# DC_Motor_Controller_with_SLAVE_OUT.net
KiCad netlist of a schematic drawn in EAGLE
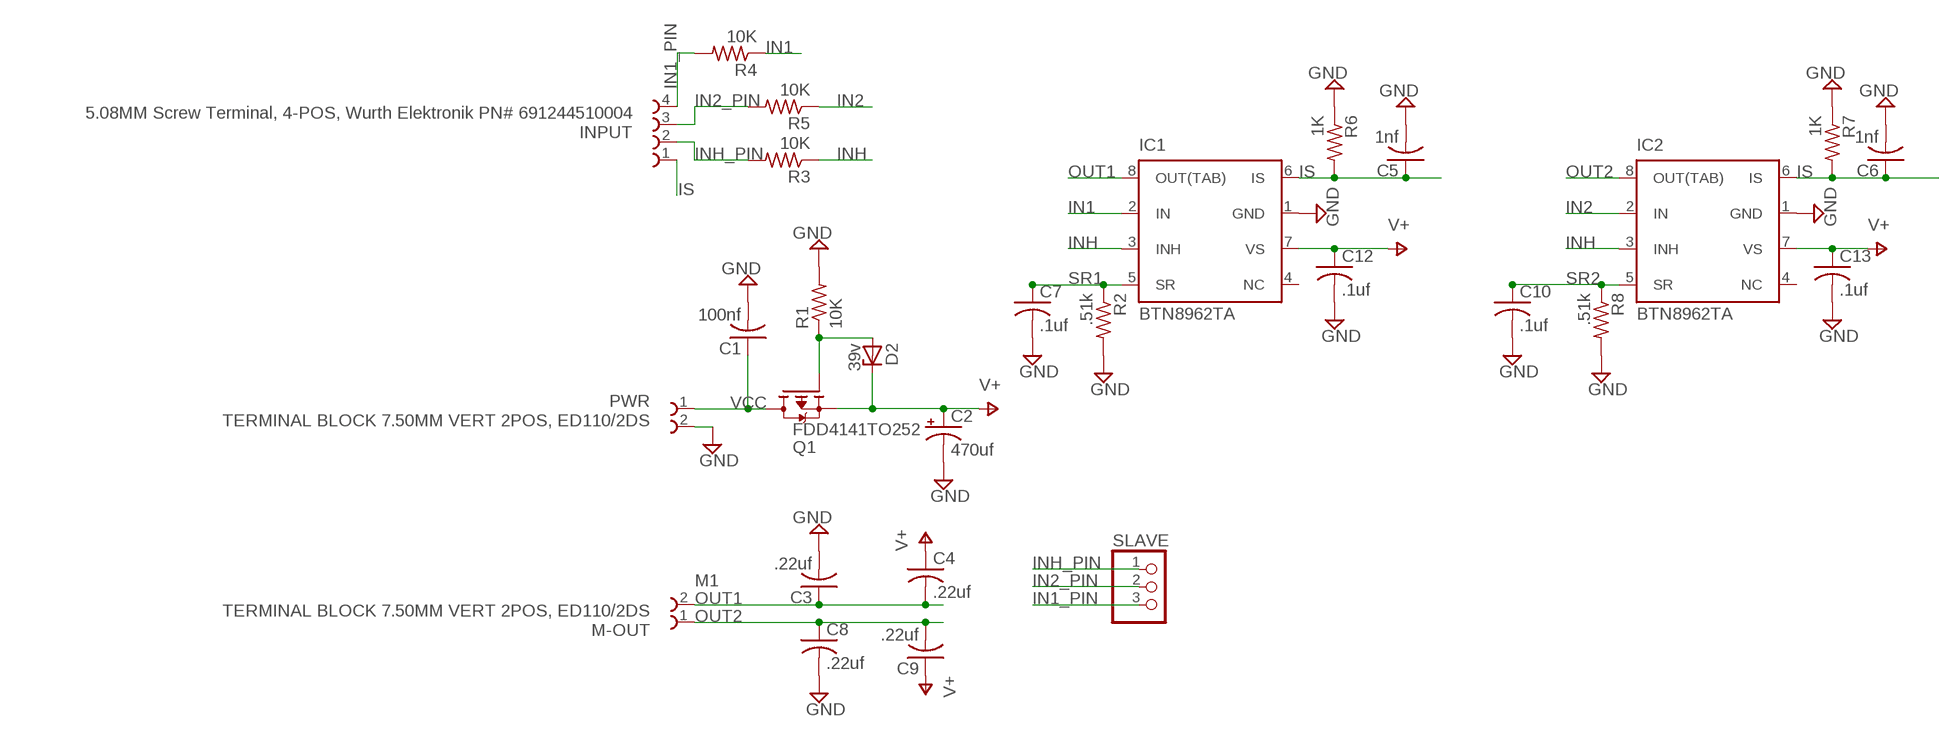
[diagram p0: schematic, sheet 1]

(export (version "E")
  (design (tool "Eeschema 10.0.6"))
  (components
    (comp (ref "C1")
      (value "100nf")
      (footprint "eagle-import:C0805")
      (libsource (lib "eagle-import") (part "C-USC0805"))
    )
    (comp (ref "C2")
      (value "470uf")
      (footprint "eagle-import:TT5D10")
      (libsource (lib "eagle-import") (part "CPOL-USTT5D10"))
    )
    (comp (ref "C3")
      (value ".22uf")
      (footprint "eagle-import:C0805")
      (libsource (lib "eagle-import") (part "C-USC0805"))
    )
    (comp (ref "C4")
      (value ".22uf")
      (footprint "eagle-import:C0805")
      (libsource (lib "eagle-import") (part "C-USC0805"))
    )
    (comp (ref "C5")
      (value "1nf")
      (footprint "eagle-import:C0805")
      (libsource (lib "eagle-import") (part "C-USC0805"))
    )
    (comp (ref "C6")
      (value "1nf")
      (footprint "eagle-import:C0805")
      (libsource (lib "eagle-import") (part "C-USC0805"))
    )
    (comp (ref "C7")
      (value ".1uf")
      (footprint "eagle-import:C0805")
      (libsource (lib "eagle-import") (part "C-USC0805"))
    )
    (comp (ref "C8")
      (value ".22uf")
      (footprint "eagle-import:C0805")
      (libsource (lib "eagle-import") (part "C-USC0805"))
    )
    (comp (ref "C9")
      (value ".22uf")
      (footprint "eagle-import:C0805")
      (libsource (lib "eagle-import") (part "C-USC0805"))
    )
    (comp (ref "C10")
      (value ".1uf")
      (footprint "eagle-import:C0805")
      (libsource (lib "eagle-import") (part "C-USC0805"))
    )
    (comp (ref "C12")
      (value ".1uf")
      (footprint "eagle-import:C0805")
      (libsource (lib "eagle-import") (part "C-USC0805"))
    )
    (comp (ref "C13")
      (value ".1uf")
      (footprint "eagle-import:C0805")
      (libsource (lib "eagle-import") (part "C-USC0805"))
    )
    (comp (ref "D2")
      (value "39v")
      (footprint "eagle-import:SMB")
      (libsource (lib "eagle-import") (part "ZENER-DIODESMB"))
    )
    (comp (ref "IC1")
      (value "BTN8962TA")
      (footprint "eagle-import:P-TO263-7-1_LG_PADS")
      (libsource (lib "eagle-import") (part "BTN8962TA"))
    )
    (comp (ref "IC2")
      (value "BTN8962TA")
      (footprint "eagle-import:P-TO263-7-1_LG_PADS")
      (libsource (lib "eagle-import") (part "BTN8962TA"))
    )
    (comp (ref "INPUT")
      (value "5.08MM Screw Terminal, 4-POS, Wurth Elektronik PN# 691244510004")
      (footprint "eagle-import:691244510004")
      (libsource (lib "eagle-import") (part "691244510004"))
    )
    (comp (ref "M-OUT")
      (value "TERMINAL BLOCK 7.50MM VERT 2POS, ED110/2DS")
      (footprint "eagle-import:7-5MM-SCREW-TERM")
      (libsource (lib "eagle-import") (part "7-5MM-SCREW-TERM"))
    )
    (comp (ref "PWR")
      (value "TERMINAL BLOCK 7.50MM VERT 2POS, ED110/2DS")
      (footprint "eagle-import:7-5MM-SCREW-TERM")
      (libsource (lib "eagle-import") (part "7-5MM-SCREW-TERM"))
    )
    (comp (ref "Q1")
      (value "FDD4141TO252")
      (footprint "eagle-import:TO252")
      (libsource (lib "eagle-import") (part "FDD4141TO252"))
    )
    (comp (ref "R1")
      (value "10K")
      (footprint "eagle-import:R0805")
      (libsource (lib "eagle-import") (part "R-US_R0805"))
    )
    (comp (ref "R2")
      (value ".51k")
      (footprint "eagle-import:R0805")
      (libsource (lib "eagle-import") (part "R-US_R0805"))
    )
    (comp (ref "R3")
      (value "10K")
      (footprint "eagle-import:R0805")
      (libsource (lib "eagle-import") (part "R-US_R0805"))
    )
    (comp (ref "R4")
      (value "10K")
      (footprint "eagle-import:R0805")
      (libsource (lib "eagle-import") (part "R-US_R0805"))
    )
    (comp (ref "R5")
      (value "10K")
      (footprint "eagle-import:R0805")
      (libsource (lib "eagle-import") (part "R-US_R0805"))
    )
    (comp (ref "R6")
      (value "1K")
      (footprint "eagle-import:R0805")
      (libsource (lib "eagle-import") (part "R-US_R0805"))
    )
    (comp (ref "R7")
      (value "1K")
      (footprint "eagle-import:R0805")
      (libsource (lib "eagle-import") (part "R-US_R0805"))
    )
    (comp (ref "R8")
      (value ".51k")
      (footprint "eagle-import:R0805")
      (libsource (lib "eagle-import") (part "R-US_R0805"))
    )
    (comp (ref "SLAVE")
      (value "PINHD-1X3CB")
      (footprint "eagle-import:1X03-CLEANBIG")
      (libsource (lib "eagle-import") (part "PINHD-1X3CB"))
    )
  )
  (nets
    (net (code "1") (name "/IN1") (class "Default")
      (node (ref "IC1") (pin "2") (pinfunction "IN_2") (pintype "input"))
      (node (ref "R4") (pin "1") (pinfunction "1_1") (pintype "passive"))
    )
    (net (code "2") (name "/IN1_PIN") (class "Default")
      (node (ref "INPUT") (pin "4") (pinfunction "4_4") (pintype "passive"))
      (node (ref "R4") (pin "2") (pinfunction "2_2") (pintype "passive"))
      (node (ref "SLAVE") (pin "3") (pinfunction "3_3") (pintype "passive"))
    )
    (net (code "3") (name "/IN2") (class "Default")
      (node (ref "IC2") (pin "2") (pinfunction "IN_2") (pintype "input"))
      (node (ref "R5") (pin "1") (pinfunction "1_1") (pintype "passive"))
    )
    (net (code "4") (name "/IN2_PIN") (class "Default")
      (node (ref "INPUT") (pin "3") (pinfunction "3_3") (pintype "passive"))
      (node (ref "R5") (pin "2") (pinfunction "2_2") (pintype "passive"))
      (node (ref "SLAVE") (pin "2") (pinfunction "2_2") (pintype "passive"))
    )
    (net (code "5") (name "/INH") (class "Default")
      (node (ref "IC1") (pin "3") (pinfunction "INH_3") (pintype "input"))
      (node (ref "IC2") (pin "3") (pinfunction "INH_3") (pintype "input"))
      (node (ref "R3") (pin "1") (pinfunction "1_1") (pintype "passive"))
    )
    (net (code "6") (name "/INH_PIN") (class "Default")
      (node (ref "INPUT") (pin "2") (pinfunction "2_2") (pintype "passive"))
      (node (ref "R3") (pin "2") (pinfunction "2_2") (pintype "passive"))
      (node (ref "SLAVE") (pin "1") (pinfunction "1_1") (pintype "passive"))
    )
    (net (code "7") (name "/IS") (class "Default")
      (node (ref "C5") (pin "1") (pinfunction "1_1") (pintype "passive"))
      (node (ref "C6") (pin "1") (pinfunction "1_1") (pintype "passive"))
      (node (ref "IC1") (pin "6") (pinfunction "IS_6") (pintype "output"))
      (node (ref "IC2") (pin "6") (pinfunction "IS_6") (pintype "output"))
      (node (ref "INPUT") (pin "1") (pinfunction "1_1") (pintype "passive"))
      (node (ref "R6") (pin "2") (pinfunction "2_2") (pintype "passive"))
      (node (ref "R7") (pin "2") (pinfunction "2_2") (pintype "passive"))
    )
    (net (code "8") (name "/OUT1") (class "Default")
      (node (ref "C3") (pin "1") (pinfunction "1_1") (pintype "passive"))
      (node (ref "C4") (pin "2") (pinfunction "2_2") (pintype "passive"))
      (node (ref "IC1") (pin "8") (pinfunction "OUT(TAB)_8") (pintype "output"))
      (node (ref "M-OUT") (pin "2") (pinfunction "2_2") (pintype "passive"))
    )
    (net (code "9") (name "/OUT2") (class "Default")
      (node (ref "C8") (pin "1") (pinfunction "1_1") (pintype "passive"))
      (node (ref "C9") (pin "2") (pinfunction "2_2") (pintype "passive"))
      (node (ref "IC2") (pin "8") (pinfunction "OUT(TAB)_8") (pintype "output"))
      (node (ref "M-OUT") (pin "1") (pinfunction "1_1") (pintype "passive"))
    )
    (net (code "10") (name "/SR1") (class "Default")
      (node (ref "C7") (pin "1") (pinfunction "1_1") (pintype "passive"))
      (node (ref "IC1") (pin "5") (pinfunction "SR_5") (pintype "input"))
      (node (ref "R2") (pin "1") (pinfunction "1_1") (pintype "passive"))
    )
    (net (code "11") (name "/SR2") (class "Default")
      (node (ref "C10") (pin "1") (pinfunction "1_1") (pintype "passive"))
      (node (ref "IC2") (pin "5") (pinfunction "SR_5") (pintype "input"))
      (node (ref "R8") (pin "1") (pinfunction "1_1") (pintype "passive"))
    )
    (net (code "12") (name "/VCC") (class "Default")
      (node (ref "C1") (pin "1") (pinfunction "1_1") (pintype "passive"))
      (node (ref "PWR") (pin "1") (pinfunction "1_1") (pintype "passive"))
      (node (ref "Q1") (pin "3") (pinfunction "D_3") (pintype "passive"))
    )
    (net (code "13") (name "GND") (class "Default")
      (node (ref "C1") (pin "2") (pinfunction "2_2") (pintype "passive"))
      (node (ref "C10") (pin "2") (pinfunction "2_2") (pintype "passive"))
      (node (ref "C12") (pin "2") (pinfunction "2_2") (pintype "passive"))
      (node (ref "C13") (pin "2") (pinfunction "2_2") (pintype "passive"))
      (node (ref "C2") (pin "-") (pinfunction "-_-") (pintype "passive"))
      (node (ref "C3") (pin "2") (pinfunction "2_2") (pintype "passive"))
      (node (ref "C5") (pin "2") (pinfunction "2_2") (pintype "passive"))
      (node (ref "C6") (pin "2") (pinfunction "2_2") (pintype "passive"))
      (node (ref "C7") (pin "2") (pinfunction "2_2") (pintype "passive"))
      (node (ref "C8") (pin "2") (pinfunction "2_2") (pintype "passive"))
      (node (ref "IC1") (pin "1") (pinfunction "GND_1") (pintype "power_in"))
      (node (ref "IC2") (pin "1") (pinfunction "GND_1") (pintype "power_in"))
      (node (ref "PWR") (pin "2") (pinfunction "2_2") (pintype "passive"))
      (node (ref "R1") (pin "2") (pinfunction "2_2") (pintype "passive"))
      (node (ref "R2") (pin "2") (pinfunction "2_2") (pintype "passive"))
      (node (ref "R6") (pin "1") (pinfunction "1_1") (pintype "passive"))
      (node (ref "R7") (pin "1") (pinfunction "1_1") (pintype "passive"))
      (node (ref "R8") (pin "2") (pinfunction "2_2") (pintype "passive"))
    )
    (net (code "14") (name "Net-(Q1-G)") (class "Default")
      (node (ref "D2") (pin "A") (pinfunction "A_A") (pintype "passive"))
      (node (ref "Q1") (pin "1") (pinfunction "G_1") (pintype "passive"))
      (node (ref "R1") (pin "1") (pinfunction "1_1") (pintype "passive"))
    )
    (net (code "15") (name "V+") (class "Default")
      (node (ref "C12") (pin "1") (pinfunction "1_1") (pintype "passive"))
      (node (ref "C13") (pin "1") (pinfunction "1_1") (pintype "passive"))
      (node (ref "C2") (pin "+") (pinfunction "+_+") (pintype "passive"))
      (node (ref "C4") (pin "1") (pinfunction "1_1") (pintype "passive"))
      (node (ref "C9") (pin "1") (pinfunction "1_1") (pintype "passive"))
      (node (ref "D2") (pin "C") (pinfunction "C_C") (pintype "passive"))
      (node (ref "IC1") (pin "7") (pinfunction "VS_7") (pintype "power_in"))
      (node (ref "IC2") (pin "7") (pinfunction "VS_7") (pintype "power_in"))
      (node (ref "Q1") (pin "2") (pinfunction "S_2") (pintype "passive"))
    )
    (net (code "16") (name "unconnected-(IC1-NC-Pad4)") (class "Default")
      (node (ref "IC1") (pin "4") (pinfunction "NC_4") (pintype "no_connect"))
    )
    (net (code "17") (name "unconnected-(IC2-NC-Pad4)") (class "Default")
      (node (ref "IC2") (pin "4") (pinfunction "NC_4") (pintype "no_connect"))
    )
  )
)
